# H1DR10.net
KiCad netlist of a schematic drawn in EAGLE
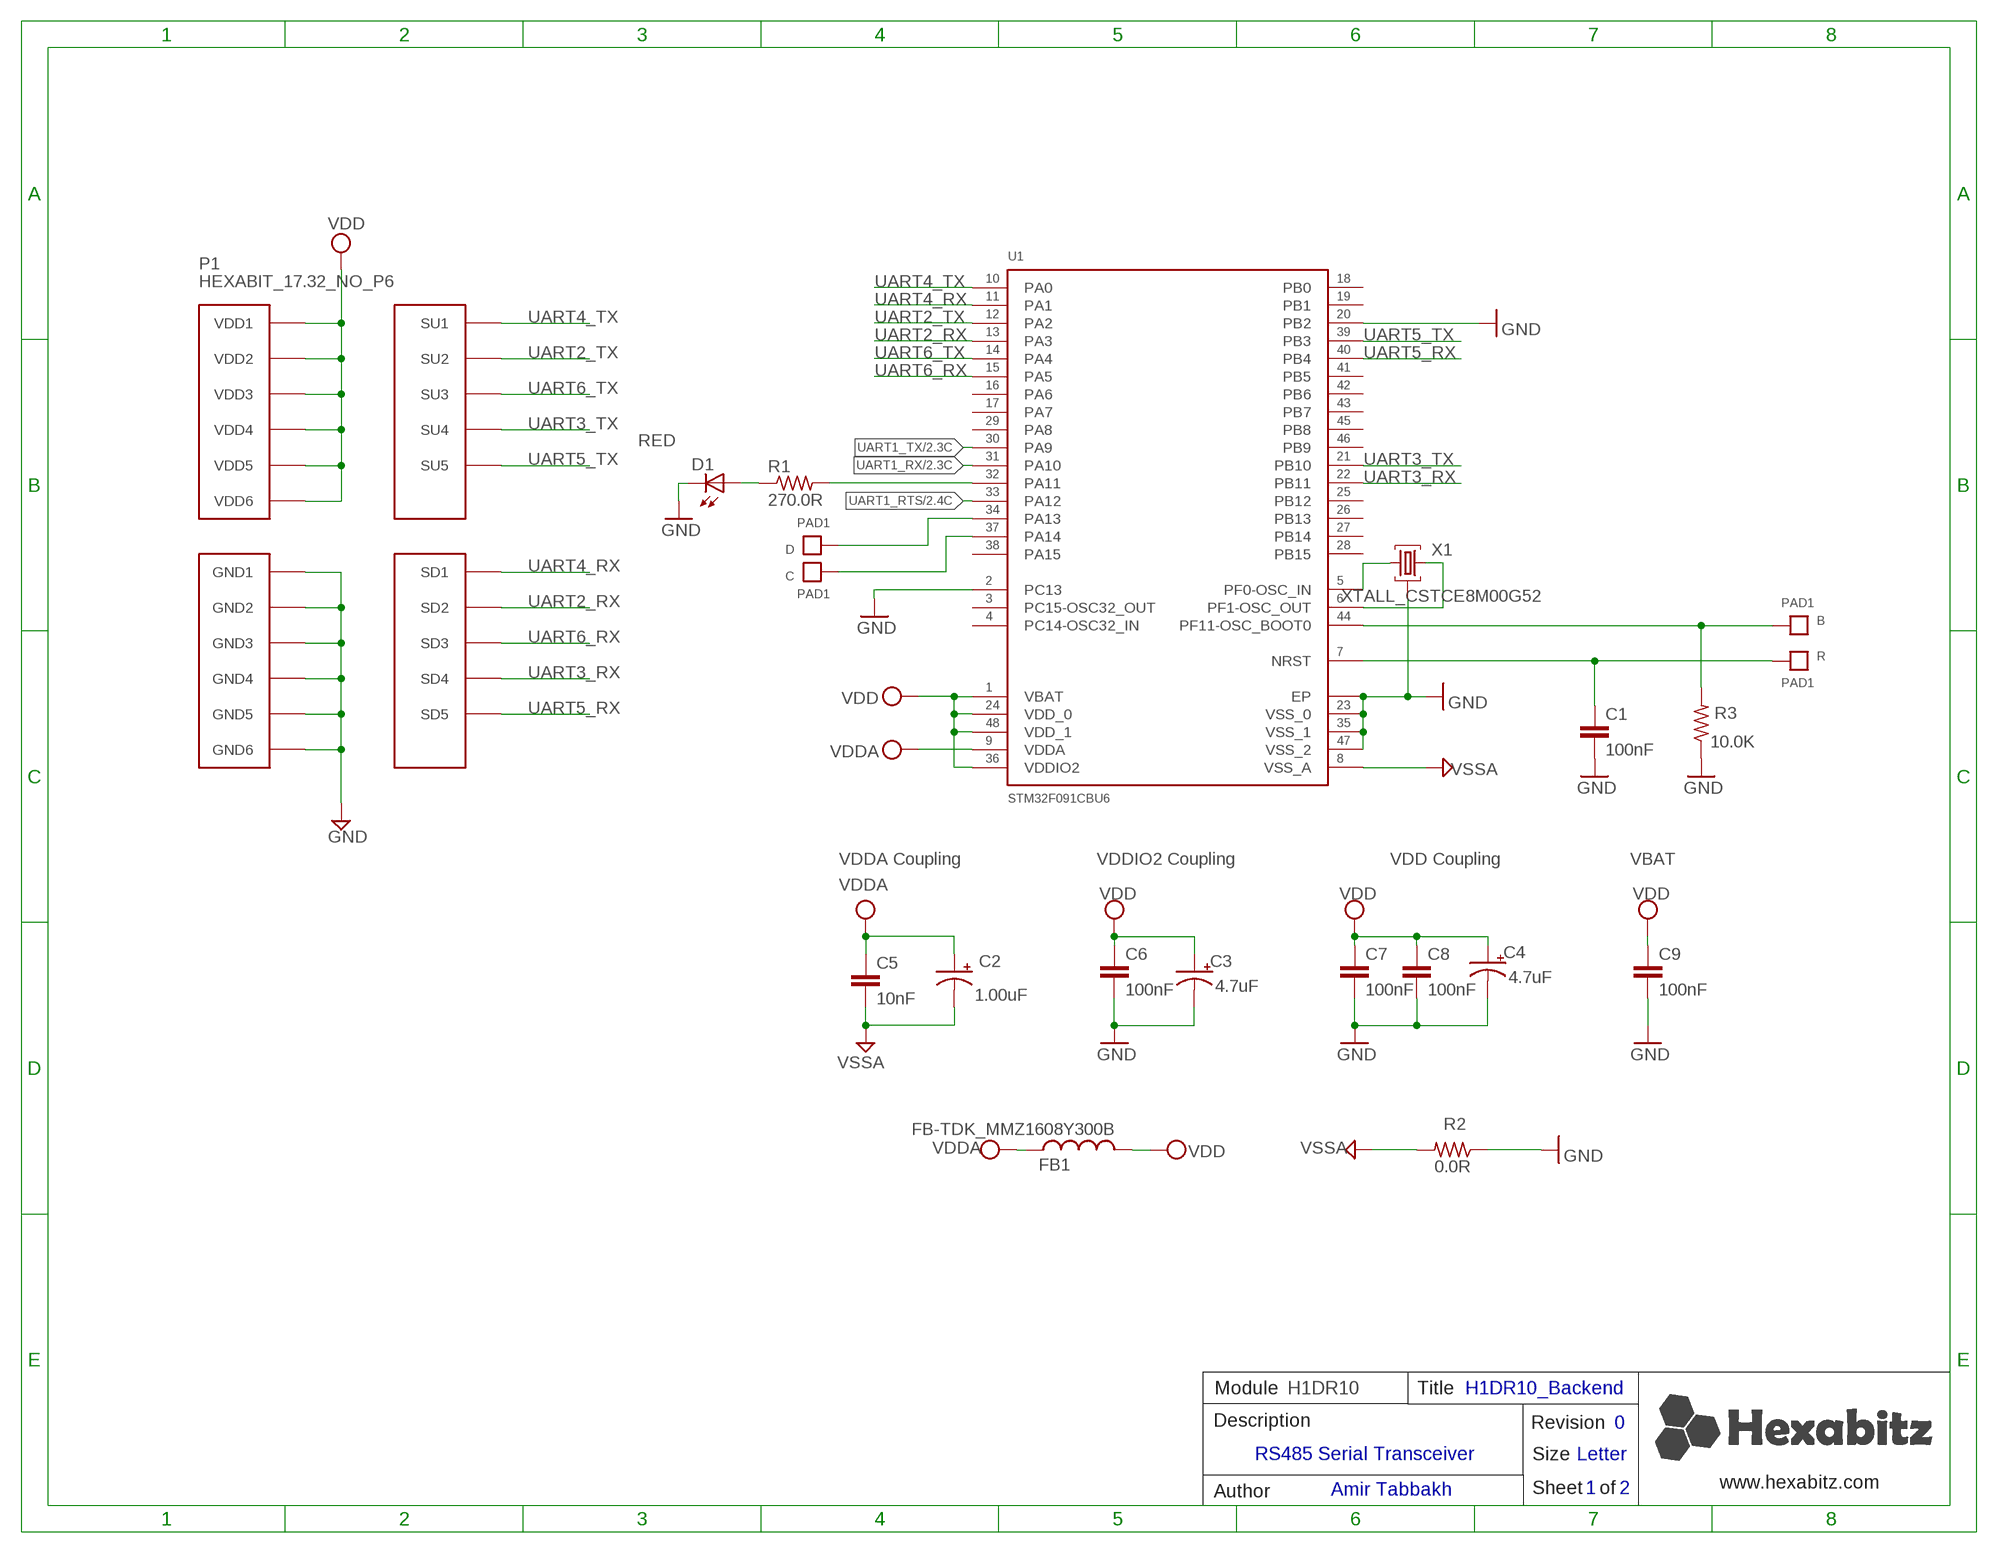
[diagram p0: schematic, sheet 1]
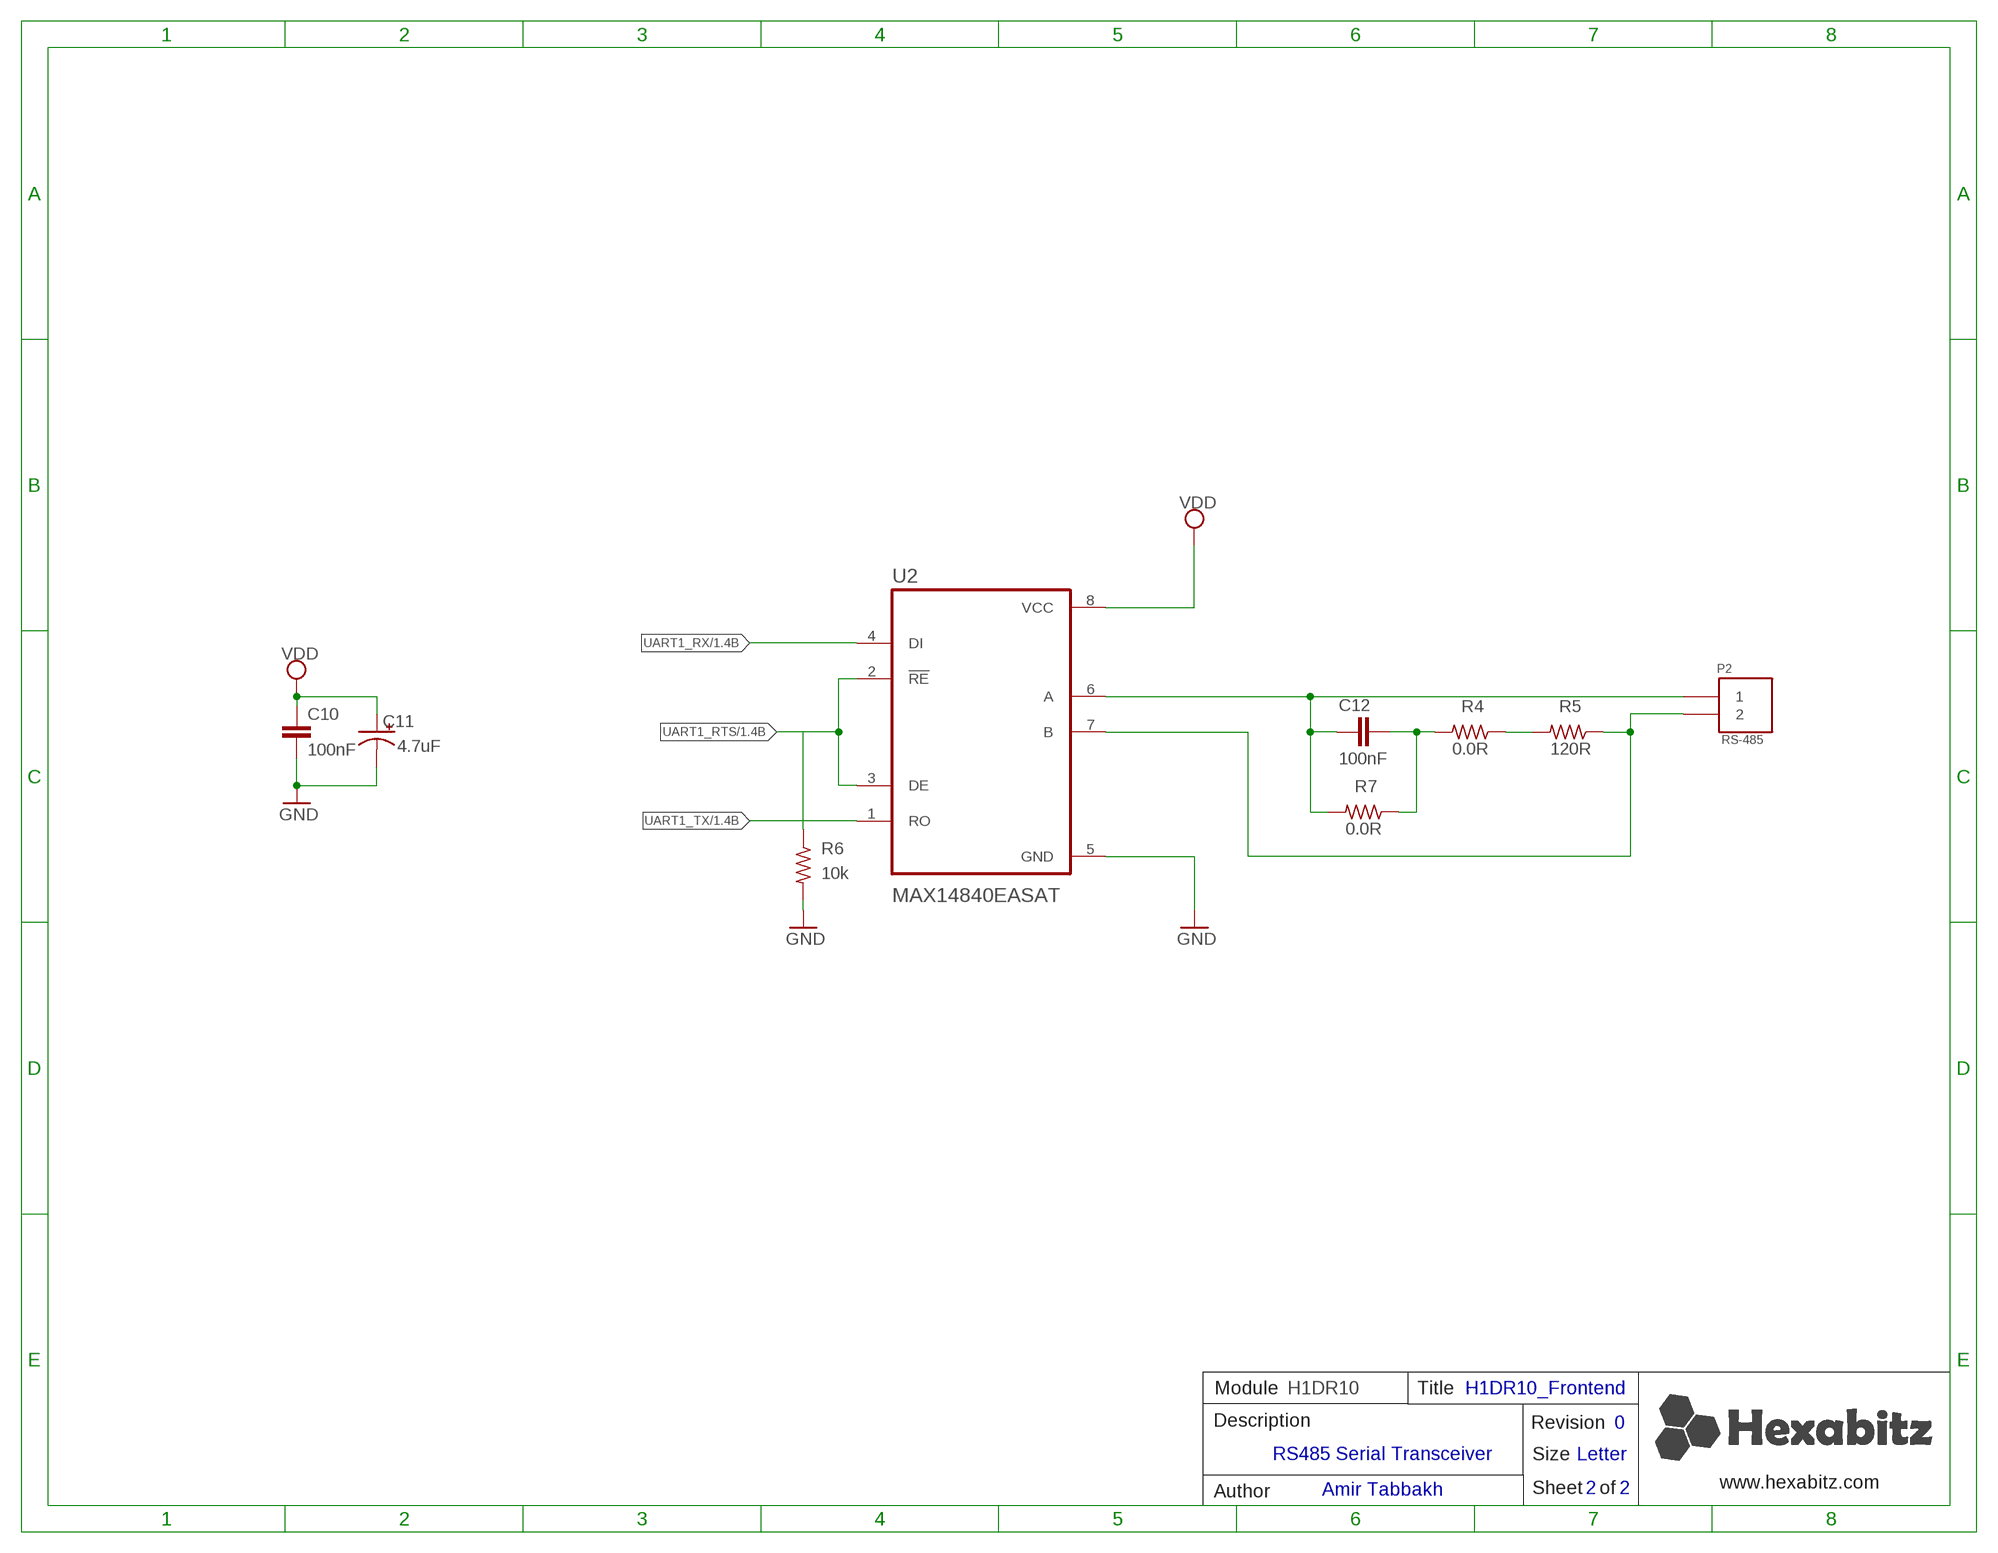
[diagram p1: schematic, sheet 2]

(export (version "E")
  (design (tool "Eeschema 10.0.6"))
  (components
    (comp (ref "C10")
      (value "100nF")
      (footprint "eagle-import:C-0603")
      (fields
        (field (name "CAPACITANCE") "100nF")
        (field (name "MFN") "KEMET")
        (field (name "MPN") "C0603C104K8RACTU")
        (field (name "OCTOPART_URL") "https://octopart.com/c0603c104k8ractu-kemet-145075?r=sp&s=9bS9ASSwSEqMCE9KBEQZ0g")
        (field (name "TOLERANCE") "10%")
        (field (name "VOLTAGE_RATING") "10V")
      )
      (libsource (lib "eagle-import") (part "C-0603"))
    )
    (comp (ref "C11")
      (value "4.7uF")
      (footprint "eagle-import:C-0805-POL")
      (fields
        (field (name "CAPACITANCE") "4.7uF")
        (field (name "MFN") "Murata")
        (field (name "MPN") "GRM21BC81E475KA12L")
        (field (name "OCTOPART_URL") "https://octopart.com/grm21bc81e475ka12l-murata-10331911?r=sp&s=RY3qZSD8T6mG6TC9CHI5qQ")
        (field (name "TOLERANCE") "10%")
        (field (name "VOLTAGE_RATING") "25V")
      )
      (libsource (lib "eagle-import") (part "C-0805-POL"))
    )
    (comp (ref "C12")
      (value "100nF")
      (footprint "eagle-import:C-0603")
      (fields
        (field (name "CAPACITANCE") "100nF")
        (field (name "MFN") "AVX")
        (field (name "MPN") "0603YC104K4T2A")
        (field (name "OCTOPART_URL") "https://octopart.com/0603yc104k4t2a-avx+interconnect+%2F+elco-8120651")
        (field (name "TOLERANCE") "10%")
        (field (name "VOLTAGE_RATING") "16V")
      )
      (libsource (lib "eagle-import") (part "C-0603"))
    )
    (comp (ref "P2")
      (value "RS-485")
      (footprint "eagle-import:1546111-2")
      (fields (field (name "MPN") "1546111-2"))
      (libsource (lib "eagle-import") (part "1546111-2"))
    )
    (comp (ref "R4")
      (value "0.0R")
      (footprint "eagle-import:R-0603")
      (fields
        (field (name "MFN") "Vishay")
        (field (name "MPN") "CRCW06030000Z0EA")
        (field (name "OCTOPART_URL") "https://octopart.com/crcw06030000z0ea-vishay-39556096#")
        (field (name "RESISTANCE") "0.0 Ohm")
      )
      (libsource (lib "eagle-import") (part "R-0603"))
    )
    (comp (ref "R5")
      (value "120R")
      (footprint "eagle-import:R-0805")
      (fields
        (field (name "MFN") "Panasonic")
        (field (name "MPN") "ERJP6WF1200V")
        (field (name "OCTOPART_URL") "https://octopart.com/erjp6wf1200v-panasonic-25949195?r=sp#")
        (field (name "RESISTANCE") "120R")
        (field (name "TOLERANCE") "1%")
      )
      (libsource (lib "eagle-import") (part "R-0805"))
    )
    (comp (ref "R6")
      (value "10k")
      (footprint "eagle-import:R-0603")
      (fields
        (field (name "MFN") "Vishay")
        (field (name "MPN") "CRCW060310K0JNEB")
        (field (name "OCTOPART_URL") "https://octopart.com/crcw060310k0jneb-vishay+dale-46603268")
        (field (name "RESISTANCE") "10k")
        (field (name "TOLERANCE") "5%")
      )
      (libsource (lib "eagle-import") (part "R-0603"))
    )
    (comp (ref "R7")
      (value "0.0R")
      (footprint "eagle-import:R-0603")
      (fields
        (field (name "MFN") "Vishay")
        (field (name "MPN") "CRCW06030000Z0EA")
        (field (name "OCTOPART_URL") "https://octopart.com/crcw06030000z0ea-vishay-39556096#")
        (field (name "RESISTANCE") "0.0 Ohm")
      )
      (libsource (lib "eagle-import") (part "R-0603"))
    )
    (comp (ref "U2")
      (value "MAX14840EASAT")
      (footprint "eagle-import:SOIC127P600X175-8N")
      (fields (field (name "MPN") "MAX14840EASA+"))
      (libsource (lib "eagle-import") (part "MAX14840EASAT"))
    )
    (comp (ref "B")
      (value "PAD1")
      (footprint "eagle-import:PAD1")
      (libsource (lib "eagle-import") (part "PAD1"))
    )
    (comp (ref "C")
      (value "PAD1")
      (footprint "eagle-import:PAD1")
      (libsource (lib "eagle-import") (part "PAD1"))
    )
    (comp (ref "C1")
      (value "100nF")
      (footprint "eagle-import:C-0603")
      (fields
        (field (name "CAPACITANCE") "100nF")
        (field (name "MFN") "KEMET")
        (field (name "MPN") "C0603C104K8RACTU")
        (field (name "OCTOPART_URL") "https://octopart.com/c0603c104k8ractu-kemet-145075?r=sp&s=9bS9ASSwSEqMCE9KBEQZ0g")
        (field (name "TOLERANCE") "10%")
        (field (name "VOLTAGE_RATING") "10V")
      )
      (libsource (lib "eagle-import") (part "C-0603"))
    )
    (comp (ref "C2")
      (value "1.00uF")
      (footprint "eagle-import:C-0805-POL")
      (fields
        (field (name "CAPACITANCE") "1.00uF")
        (field (name "MFN") "Yageo")
        (field (name "MPN") "CC0805KKX7R7BB105")
        (field (name "OCTOPART_URL") "https://octopart.com/cc0805kkx7r7bb105-yageo-8376555?r=sp&s=YKl1wwtkROau_X5nniH2ig")
        (field (name "TOLERANCE") "10%")
        (field (name "VOLTAGE_RATING") "16V")
      )
      (libsource (lib "eagle-import") (part "C-0805-POL"))
    )
    (comp (ref "C3")
      (value "4.7uF")
      (footprint "eagle-import:C-0805-POL")
      (fields
        (field (name "CAPACITANCE") "4.7uF")
        (field (name "MFN") "Murata")
        (field (name "MPN") "GRM21BC81E475KA12L")
        (field (name "OCTOPART_URL") "https://octopart.com/grm21bc81e475ka12l-murata-10331911?r=sp&s=RY3qZSD8T6mG6TC9CHI5qQ")
        (field (name "TOLERANCE") "10%")
        (field (name "VOLTAGE_RATING") "25V")
      )
      (libsource (lib "eagle-import") (part "C-0805-POL"))
    )
    (comp (ref "C4")
      (value "4.7uF")
      (footprint "eagle-import:C-0805-POL")
      (fields
        (field (name "CAPACITANCE") "4.7uF")
        (field (name "MFN") "Murata")
        (field (name "MPN") "GRM21BC81E475KA12L")
        (field (name "OCTOPART_URL") "https://octopart.com/grm21bc81e475ka12l-murata-10331911?r=sp&s=RY3qZSD8T6mG6TC9CHI5qQ")
        (field (name "TOLERANCE") "10%")
        (field (name "VOLTAGE_RATING") "25V")
      )
      (libsource (lib "eagle-import") (part "C-0805-POL"))
    )
    (comp (ref "C5")
      (value "10nF")
      (footprint "eagle-import:C-0603")
      (fields
        (field (name "CAPACITANCE") "10nF")
        (field (name "MFN") "KEMET")
        (field (name "MPN") "C0603C103K5RACTU")
        (field (name "OCTOPART_URL") "https://octopart.com/c0603c103k5ractu-kemet-133094?r=sp&s=R_iPBxLnSmGqhkU2rIMFpg")
        (field (name "TOLERANCE") "10%")
        (field (name "VOLTAGE_RATING") "50V")
      )
      (libsource (lib "eagle-import") (part "C-0603"))
    )
    (comp (ref "C6")
      (value "100nF")
      (footprint "eagle-import:C-0603")
      (fields
        (field (name "CAPACITANCE") "100nF")
        (field (name "MFN") "KEMET")
        (field (name "MPN") "C0603C104K8RACTU")
        (field (name "OCTOPART_URL") "https://octopart.com/c0603c104k8ractu-kemet-145075?r=sp&s=9bS9ASSwSEqMCE9KBEQZ0g")
        (field (name "TOLERANCE") "10%")
        (field (name "VOLTAGE_RATING") "10V")
      )
      (libsource (lib "eagle-import") (part "C-0603"))
    )
    (comp (ref "C7")
      (value "100nF")
      (footprint "eagle-import:C-0603")
      (fields
        (field (name "CAPACITANCE") "100nF")
        (field (name "MFN") "KEMET")
        (field (name "MPN") "C0603C104K8RACTU")
        (field (name "OCTOPART_URL") "https://octopart.com/c0603c104k8ractu-kemet-145075?r=sp&s=9bS9ASSwSEqMCE9KBEQZ0g")
        (field (name "TOLERANCE") "10%")
        (field (name "VOLTAGE_RATING") "10")
      )
      (libsource (lib "eagle-import") (part "C-0603"))
    )
    (comp (ref "C8")
      (value "100nF")
      (footprint "eagle-import:C-0603")
      (fields
        (field (name "CAPACITANCE") "100nF")
        (field (name "MFN") "KEMET")
        (field (name "MPN") "C0603C104K8RACTU")
        (field (name "OCTOPART_URL") "https://octopart.com/c0603c104k8ractu-kemet-145075?r=sp&s=9bS9ASSwSEqMCE9KBEQZ0g")
        (field (name "TOLERANCE") "10%")
        (field (name "VOLTAGE_RATING") "10V")
      )
      (libsource (lib "eagle-import") (part "C-0603"))
    )
    (comp (ref "C9")
      (value "100nF")
      (footprint "eagle-import:C-0603")
      (fields
        (field (name "CAPACITANCE") "100nF")
        (field (name "MFN") "KEMET")
        (field (name "MPN") "C0603C104K8RACTU")
        (field (name "OCTOPART_URL") "https://octopart.com/c0603c104k8ractu-kemet-145075?r=sp&s=9bS9ASSwSEqMCE9KBEQZ0g")
        (field (name "TOLERANCE") "10V")
        (field (name "VOLTAGE_RATING") "10%")
      )
      (libsource (lib "eagle-import") (part "C-0603"))
    )
    (comp (ref "D")
      (value "PAD1")
      (footprint "eagle-import:PAD1")
      (libsource (lib "eagle-import") (part "PAD1"))
    )
    (comp (ref "D1")
      (value "RED")
      (footprint "eagle-import:VLMS1300-GS08")
      (fields
        (field (name "MPN") "VLMS1300-GS08")
        (field (name "MFN") "Vishay")
        (field (name "MPN_1") "VLMS1300-GS08")
        (field (name "OCTOPART_URL") "https://octopart.com/vlms1300-gs08-vishay-21709201?r=sp&s=_gcP4_q8T1SC6PJQPTQ9yA")
      )
      (libsource (lib "eagle-import") (part "VLMS1300-GS08"))
    )
    (comp (ref "FB1")
      (value "FB-TDK_MMZ1608Y300B")
      (footprint "eagle-import:FB-TDK_MMZ1608Y300B")
      (fields
        (field (name "MFN") "TDK ")
        (field (name "MPN") "MMZ1608Y300B")
        (field (name "OCTOPART_URL") "https://octopart.com/mmz1608y300b-tdk-368280?r=sp&s=cd9_2ZEqQ9q9UNBuQgHAiA")
      )
      (libsource (lib "eagle-import") (part "FB-TDK_MMZ1608Y300B"))
    )
    (comp (ref "P1")
      (value "HEXABIT_17.32_NO_P6")
      (footprint "eagle-import:HEXABIT_17.32_NO_P6")
      (libsource (lib "eagle-import") (part "HEXABIT_?_NO_P617.32"))
    )
    (comp (ref "R")
      (value "PAD1")
      (footprint "eagle-import:PAD1")
      (libsource (lib "eagle-import") (part "PAD1"))
    )
    (comp (ref "R1")
      (value "270.0R")
      (footprint "eagle-import:R-0603")
      (fields
        (field (name "MFN") "Yageo")
        (field (name "MPN") "RC0603FR-07270RL")
        (field (name "OCTOPART_URL") "https://octopart.com/search?q=RC0603FR-07270RL&start=0")
        (field (name "RESISTANCE") "270.0 Ohm")
        (field (name "TOLERANCE") "1%")
      )
      (libsource (lib "eagle-import") (part "R-0603"))
    )
    (comp (ref "R2")
      (value "0.0R")
      (footprint "eagle-import:R-0603")
      (fields
        (field (name "MFN") "Yageo")
        (field (name "MPN") "RC0603JR-070RL")
        (field (name "OCTOPART_URL") "https://octopart.com/rc0603jr-070rl-yageo-1241539?r=sp&s=X2NteqRjRNWrnx42Y0aliA")
        (field (name "RESISTANCE") "0.0 Ohm")
      )
      (libsource (lib "eagle-import") (part "R-0603"))
    )
    (comp (ref "R3")
      (value "10.0K")
      (footprint "eagle-import:R-0603")
      (fields
        (field (name "MFN") "Yageo")
        (field (name "MPN") "RC0603JR-0710KL")
        (field (name "OCTOPART_URL") "https://octopart.com/search?q=RC0603JR-0710KL&start=0")
        (field (name "RESISTANCE") "10.0K Ohm")
        (field (name "TOLERANCE") "5%")
      )
      (libsource (lib "eagle-import") (part "R-0603"))
    )
    (comp (ref "U1")
      (value "STM32F091CBU6")
      (footprint "eagle-import:STM32F091CBU6")
      (libsource (lib "eagle-import") (part "STM32F091CBU6"))
    )
    (comp (ref "X1")
      (value "XTALL_CSTCE8M00G52")
      (footprint "eagle-import:XTALL_CSTCE8M00G52")
      (fields (field (name "MPN") "CSTCE8M00G52Z-R0"))
      (libsource (lib "eagle-import") (part "XTALL_CSTCE8M00G52"))
    )
  )
  (nets
    (net (code "1") (name "GND") (class "Default")
      (node (ref "C1") (pin "2") (pinfunction "2_2") (pintype "passive"))
      (node (ref "C10") (pin "2") (pinfunction "2_2") (pintype "passive"))
      (node (ref "C11") (pin "2") (pinfunction "-_2") (pintype "passive"))
      (node (ref "C3") (pin "2") (pinfunction "-_2") (pintype "passive"))
      (node (ref "C4") (pin "2") (pinfunction "-_2") (pintype "passive"))
      (node (ref "C6") (pin "2") (pinfunction "2_2") (pintype "passive"))
      (node (ref "C7") (pin "2") (pinfunction "2_2") (pintype "passive"))
      (node (ref "C8") (pin "2") (pinfunction "2_2") (pintype "passive"))
      (node (ref "C9") (pin "2") (pinfunction "2_2") (pintype "passive"))
      (node (ref "D1") (pin "C") (pinfunction "C_C") (pintype "passive"))
      (node (ref "P1") (pin "PAD_PD10") (pinfunction "GND4_PAD_PD10") (pintype "power_in"))
      (node (ref "P1") (pin "PAD_PD11") (pinfunction "GND5_PAD_PD11") (pintype "power_in"))
      (node (ref "P1") (pin "PAD_PD12") (pinfunction "GND6_PAD_PD12") (pintype "power_in"))
      (node (ref "P1") (pin "PAD_PD7") (pinfunction "GND1_PAD_PD7") (pintype "power_in"))
      (node (ref "P1") (pin "PAD_PD8") (pinfunction "GND2_PAD_PD8") (pintype "power_in"))
      (node (ref "P1") (pin "PAD_PD9") (pinfunction "GND3_PAD_PD9") (pintype "power_in"))
      (node (ref "R2") (pin "1") (pinfunction "1_1") (pintype "passive"))
      (node (ref "R3") (pin "1") (pinfunction "1_1") (pintype "passive"))
      (node (ref "R6") (pin "2") (pinfunction "2_2") (pintype "passive"))
      (node (ref "U1") (pin "EP") (pinfunction "EP_EP") (pintype "power_in"))
      (node (ref "U1") (pin "P$2") (pinfunction "PC13_P$2") (pintype "bidirectional"))
      (node (ref "U1") (pin "P$20") (pinfunction "PB2_P$20") (pintype "bidirectional"))
      (node (ref "U1") (pin "P$23") (pinfunction "VSS_0_P$23") (pintype "power_in"))
      (node (ref "U1") (pin "P$35") (pinfunction "VSS_1_P$35") (pintype "power_in"))
      (node (ref "U1") (pin "P$47") (pinfunction "VSS_2_P$47") (pintype "power_in"))
      (node (ref "U2") (pin "5") (pinfunction "GND_5") (pintype "power_in"))
      (node (ref "X1") (pin "P$2") (pinfunction "2_P$2") (pintype "passive"))
    )
    (net (code "2") (name "Net-(C12-Pad2)") (class "Default")
      (node (ref "C12") (pin "2") (pinfunction "2_2") (pintype "passive"))
      (node (ref "R4") (pin "2") (pinfunction "2_2") (pintype "passive"))
      (node (ref "R7") (pin "1") (pinfunction "1_1") (pintype "passive"))
    )
    (net (code "3") (name "Net-(D1-PadA)") (class "Default")
      (node (ref "D1") (pin "A") (pinfunction "A_A") (pintype "passive"))
      (node (ref "R1") (pin "1") (pinfunction "1_1") (pintype "passive"))
    )
    (net (code "4") (name "Net-(R4-Pad1)") (class "Default")
      (node (ref "R4") (pin "1") (pinfunction "1_1") (pintype "passive"))
      (node (ref "R5") (pin "2") (pinfunction "2_2") (pintype "passive"))
    )
    (net (code "5") (name "Net-(U1-NRST)") (class "Default")
      (node (ref "C1") (pin "1") (pinfunction "1_1") (pintype "passive"))
      (node (ref "R") (pin "P$1") (pinfunction "P$1_P$1") (pintype "passive"))
      (node (ref "R") (pin "P$2") (pinfunction "P$1_P$2") (pintype "passive"))
      (node (ref "U1") (pin "P$7") (pinfunction "NRST_P$7") (pintype "passive"))
    )
    (net (code "6") (name "Net-(U1-PA11)") (class "Default")
      (node (ref "R1") (pin "2") (pinfunction "2_2") (pintype "passive"))
      (node (ref "U1") (pin "P$32") (pinfunction "PA11_P$32") (pintype "bidirectional"))
    )
    (net (code "7") (name "Net-(U1-PA13)") (class "Default")
      (node (ref "D") (pin "P$1") (pinfunction "P$1_P$1") (pintype "passive"))
      (node (ref "D") (pin "P$2") (pinfunction "P$1_P$2") (pintype "passive"))
      (node (ref "U1") (pin "P$34") (pinfunction "PA13_P$34") (pintype "bidirectional"))
    )
    (net (code "8") (name "Net-(U1-PA14)") (class "Default")
      (node (ref "C") (pin "P$1") (pinfunction "P$1_P$1") (pintype "passive"))
      (node (ref "C") (pin "P$2") (pinfunction "P$1_P$2") (pintype "passive"))
      (node (ref "U1") (pin "P$37") (pinfunction "PA14_P$37") (pintype "bidirectional"))
    )
    (net (code "9") (name "Net-(U1-PF0-OSC_IN)") (class "Default")
      (node (ref "U1") (pin "P$5") (pinfunction "PF0-OSC_IN_P$5") (pintype "bidirectional"))
      (node (ref "X1") (pin "P$1") (pinfunction "1_P$1") (pintype "passive"))
    )
    (net (code "10") (name "Net-(U1-PF1-OSC_OUT)") (class "Default")
      (node (ref "U1") (pin "P$6") (pinfunction "PF1-OSC_OUT_P$6") (pintype "bidirectional"))
      (node (ref "X1") (pin "P$3") (pinfunction "3_P$3") (pintype "passive"))
    )
    (net (code "11") (name "Net-(U1-PF11-OSC_BOOT0)") (class "Default")
      (node (ref "B") (pin "P$1") (pinfunction "P$1_P$1") (pintype "passive"))
      (node (ref "B") (pin "P$2") (pinfunction "P$1_P$2") (pintype "passive"))
      (node (ref "R3") (pin "2") (pinfunction "2_2") (pintype "passive"))
      (node (ref "U1") (pin "P$44") (pinfunction "PF11-OSC_BOOT0_P$44") (pintype "bidirectional"))
    )
    (net (code "12") (name "Net-(U2-A)") (class "Default")
      (node (ref "C12") (pin "1") (pinfunction "1_1") (pintype "passive"))
      (node (ref "P2") (pin "1") (pinfunction "1_1") (pintype "power_in"))
      (node (ref "R7") (pin "2") (pinfunction "2_2") (pintype "passive"))
      (node (ref "U2") (pin "6") (pinfunction "A_6") (pintype "bidirectional"))
    )
    (net (code "13") (name "Net-(U2-B)") (class "Default")
      (node (ref "P2") (pin "2") (pinfunction "2_2") (pintype "power_in"))
      (node (ref "R5") (pin "1") (pinfunction "1_1") (pintype "passive"))
      (node (ref "U2") (pin "7") (pinfunction "B_7") (pintype "bidirectional"))
    )
    (net (code "14") (name "UART1_RTS") (class "Default")
      (node (ref "R6") (pin "1") (pinfunction "1_1") (pintype "passive"))
      (node (ref "U1") (pin "P$33") (pinfunction "PA12_P$33") (pintype "bidirectional"))
      (node (ref "U2") (pin "2") (pinfunction "~{RE}_2") (pintype "bidirectional"))
      (node (ref "U2") (pin "3") (pinfunction "DE_3") (pintype "bidirectional"))
    )
    (net (code "15") (name "UART1_RX") (class "Default")
      (node (ref "U1") (pin "P$31") (pinfunction "PA10_P$31") (pintype "bidirectional"))
      (node (ref "U2") (pin "4") (pinfunction "DI_4") (pintype "input"))
    )
    (net (code "16") (name "UART1_TX") (class "Default")
      (node (ref "U1") (pin "P$30") (pinfunction "PA9_P$30") (pintype "bidirectional"))
      (node (ref "U2") (pin "1") (pinfunction "RO_1") (pintype "bidirectional"))
    )
    (net (code "17") (name "UART2_RX") (class "Default")
      (node (ref "P1") (pin "PAD_PD2") (pinfunction "SD2_PAD_PD2") (pintype "bidirectional"))
      (node (ref "U1") (pin "P$13") (pinfunction "PA3_P$13") (pintype "bidirectional"))
    )
    (net (code "18") (name "UART2_TX") (class "Default")
      (node (ref "P1") (pin "PAD_PU2") (pinfunction "SU2_PAD_PU2") (pintype "bidirectional"))
      (node (ref "U1") (pin "P$12") (pinfunction "PA2_P$12") (pintype "bidirectional"))
    )
    (net (code "19") (name "UART3_RX") (class "Default")
      (node (ref "P1") (pin "PAD_PD4") (pinfunction "SD4_PAD_PD4") (pintype "bidirectional"))
      (node (ref "U1") (pin "P$22") (pinfunction "PB11_P$22") (pintype "bidirectional"))
    )
    (net (code "20") (name "UART3_TX") (class "Default")
      (node (ref "P1") (pin "PAD_PU4") (pinfunction "SU4_PAD_PU4") (pintype "bidirectional"))
      (node (ref "U1") (pin "P$21") (pinfunction "PB10_P$21") (pintype "bidirectional"))
    )
    (net (code "21") (name "UART4_RX") (class "Default")
      (node (ref "P1") (pin "PAD_PD1") (pinfunction "SD1_PAD_PD1") (pintype "bidirectional"))
      (node (ref "U1") (pin "P$11") (pinfunction "PA1_P$11") (pintype "bidirectional"))
    )
    (net (code "22") (name "UART4_TX") (class "Default")
      (node (ref "P1") (pin "PAD_PU1") (pinfunction "SU1_PAD_PU1") (pintype "bidirectional"))
      (node (ref "U1") (pin "P$10") (pinfunction "PA0_P$10") (pintype "bidirectional"))
    )
    (net (code "23") (name "UART5_RX") (class "Default")
      (node (ref "P1") (pin "PAD_PD5") (pinfunction "SD5_PAD_PD5") (pintype "bidirectional"))
      (node (ref "U1") (pin "P$40") (pinfunction "PB4_P$40") (pintype "bidirectional"))
    )
    (net (code "24") (name "UART5_TX") (class "Default")
      (node (ref "P1") (pin "PAD_PU5") (pinfunction "SU5_PAD_PU5") (pintype "bidirectional"))
      (node (ref "U1") (pin "P$39") (pinfunction "PB3_P$39") (pintype "bidirectional"))
    )
    (net (code "25") (name "UART6_RX") (class "Default")
      (node (ref "P1") (pin "PAD_PD3") (pinfunction "SD3_PAD_PD3") (pintype "bidirectional"))
      (node (ref "U1") (pin "P$15") (pinfunction "PA5_P$15") (pintype "bidirectional"))
    )
    (net (code "26") (name "UART6_TX") (class "Default")
      (node (ref "P1") (pin "PAD_PU3") (pinfunction "SU3_PAD_PU3") (pintype "bidirectional"))
      (node (ref "U1") (pin "P$14") (pinfunction "PA4_P$14") (pintype "bidirectional"))
    )
    (net (code "27") (name "VDD") (class "Default")
      (node (ref "C10") (pin "1") (pinfunction "1_1") (pintype "passive"))
      (node (ref "C11") (pin "1") (pinfunction "+_1") (pintype "passive"))
      (node (ref "C3") (pin "1") (pinfunction "+_1") (pintype "passive"))
      (node (ref "C4") (pin "1") (pinfunction "+_1") (pintype "passive"))
      (node (ref "C6") (pin "1") (pinfunction "1_1") (pintype "passive"))
      (node (ref "C7") (pin "1") (pinfunction "1_1") (pintype "passive"))
      (node (ref "C8") (pin "1") (pinfunction "1_1") (pintype "passive"))
      (node (ref "C9") (pin "1") (pinfunction "1_1") (pintype "passive"))
      (node (ref "FB1") (pin "2") (pinfunction "2_2") (pintype "passive"))
      (node (ref "P1") (pin "PAD_PU10") (pinfunction "VDD4_PAD_PU10") (pintype "power_in"))
      (node (ref "P1") (pin "PAD_PU11") (pinfunction "VDD5_PAD_PU11") (pintype "power_in"))
      (node (ref "P1") (pin "PAD_PU12") (pinfunction "VDD6_PAD_PU12") (pintype "power_in"))
      (node (ref "P1") (pin "PAD_PU7") (pinfunction "VDD1_PAD_PU7") (pintype "power_in"))
      (node (ref "P1") (pin "PAD_PU8") (pinfunction "VDD2_PAD_PU8") (pintype "power_in"))
      (node (ref "P1") (pin "PAD_PU9") (pinfunction "VDD3_PAD_PU9") (pintype "power_in"))
      (node (ref "U1") (pin "P$1") (pinfunction "VBAT_P$1") (pintype "power_in"))
      (node (ref "U1") (pin "P$24") (pinfunction "VDD_0_P$24") (pintype "power_in"))
      (node (ref "U1") (pin "P$36") (pinfunction "VDDIO2_P$36") (pintype "power_in"))
      (node (ref "U1") (pin "P$48") (pinfunction "VDD_1_P$48") (pintype "power_in"))
      (node (ref "U2") (pin "8") (pinfunction "VCC_8") (pintype "power_in"))
    )
    (net (code "28") (name "VDDA") (class "Default")
      (node (ref "C2") (pin "1") (pinfunction "+_1") (pintype "passive"))
      (node (ref "C5") (pin "1") (pinfunction "1_1") (pintype "passive"))
      (node (ref "FB1") (pin "1") (pinfunction "1_1") (pintype "passive"))
      (node (ref "U1") (pin "P$9") (pinfunction "VDDA_P$9") (pintype "power_in"))
    )
    (net (code "29") (name "VSSA") (class "Default")
      (node (ref "C2") (pin "2") (pinfunction "-_2") (pintype "passive"))
      (node (ref "C5") (pin "2") (pinfunction "2_2") (pintype "passive"))
      (node (ref "R2") (pin "2") (pinfunction "2_2") (pintype "passive"))
      (node (ref "U1") (pin "P$8") (pinfunction "VSS_A_P$8") (pintype "power_in"))
    )
    (net (code "30") (name "unconnected-(U1-PA6-PadP$16)") (class "Default")
      (node (ref "U1") (pin "P$16") (pinfunction "PA6_P$16") (pintype "bidirectional"))
    )
    (net (code "31") (name "unconnected-(U1-PA7-PadP$17)") (class "Default")
      (node (ref "U1") (pin "P$17") (pinfunction "PA7_P$17") (pintype "bidirectional"))
    )
    (net (code "32") (name "unconnected-(U1-PA8-PadP$29)") (class "Default")
      (node (ref "U1") (pin "P$29") (pinfunction "PA8_P$29") (pintype "bidirectional"))
    )
    (net (code "33") (name "unconnected-(U1-PA15-PadP$38)") (class "Default")
      (node (ref "U1") (pin "P$38") (pinfunction "PA15_P$38") (pintype "bidirectional"))
    )
    (net (code "34") (name "unconnected-(U1-PB0-PadP$18)") (class "Default")
      (node (ref "U1") (pin "P$18") (pinfunction "PB0_P$18") (pintype "bidirectional"))
    )
    (net (code "35") (name "unconnected-(U1-PB1-PadP$19)") (class "Default")
      (node (ref "U1") (pin "P$19") (pinfunction "PB1_P$19") (pintype "bidirectional"))
    )
    (net (code "36") (name "unconnected-(U1-PB5-PadP$41)") (class "Default")
      (node (ref "U1") (pin "P$41") (pinfunction "PB5_P$41") (pintype "bidirectional"))
    )
    (net (code "37") (name "unconnected-(U1-PB6-PadP$42)") (class "Default")
      (node (ref "U1") (pin "P$42") (pinfunction "PB6_P$42") (pintype "bidirectional"))
    )
    (net (code "38") (name "unconnected-(U1-PB7-PadP$43)") (class "Default")
      (node (ref "U1") (pin "P$43") (pinfunction "PB7_P$43") (pintype "bidirectional"))
    )
    (net (code "39") (name "unconnected-(U1-PB8-PadP$45)") (class "Default")
      (node (ref "U1") (pin "P$45") (pinfunction "PB8_P$45") (pintype "bidirectional"))
    )
    (net (code "40") (name "unconnected-(U1-PB9-PadP$46)") (class "Default")
      (node (ref "U1") (pin "P$46") (pinfunction "PB9_P$46") (pintype "bidirectional"))
    )
    (net (code "41") (name "unconnected-(U1-PB12-PadP$25)") (class "Default")
      (node (ref "U1") (pin "P$25") (pinfunction "PB12_P$25") (pintype "bidirectional"))
    )
    (net (code "42") (name "unconnected-(U1-PB13-PadP$26)") (class "Default")
      (node (ref "U1") (pin "P$26") (pinfunction "PB13_P$26") (pintype "bidirectional"))
    )
    (net (code "43") (name "unconnected-(U1-PB14-PadP$27)") (class "Default")
      (node (ref "U1") (pin "P$27") (pinfunction "PB14_P$27") (pintype "bidirectional"))
    )
    (net (code "44") (name "unconnected-(U1-PB15-PadP$28)") (class "Default")
      (node (ref "U1") (pin "P$28") (pinfunction "PB15_P$28") (pintype "bidirectional"))
    )
    (net (code "45") (name "unconnected-(U1-PC14-OSC32_IN-PadP$3)") (class "Default")
      (node (ref "U1") (pin "P$3") (pinfunction "PC14-OSC32_IN_P$3") (pintype "bidirectional"))
    )
    (net (code "46") (name "unconnected-(U1-PC15-OSC32_OUT-PadP$4)") (class "Default")
      (node (ref "U1") (pin "P$4") (pinfunction "PC15-OSC32_OUT_P$4") (pintype "bidirectional"))
    )
  )
)
